# Dual_v12.net
KiCad netlist of a schematic drawn in EAGLE
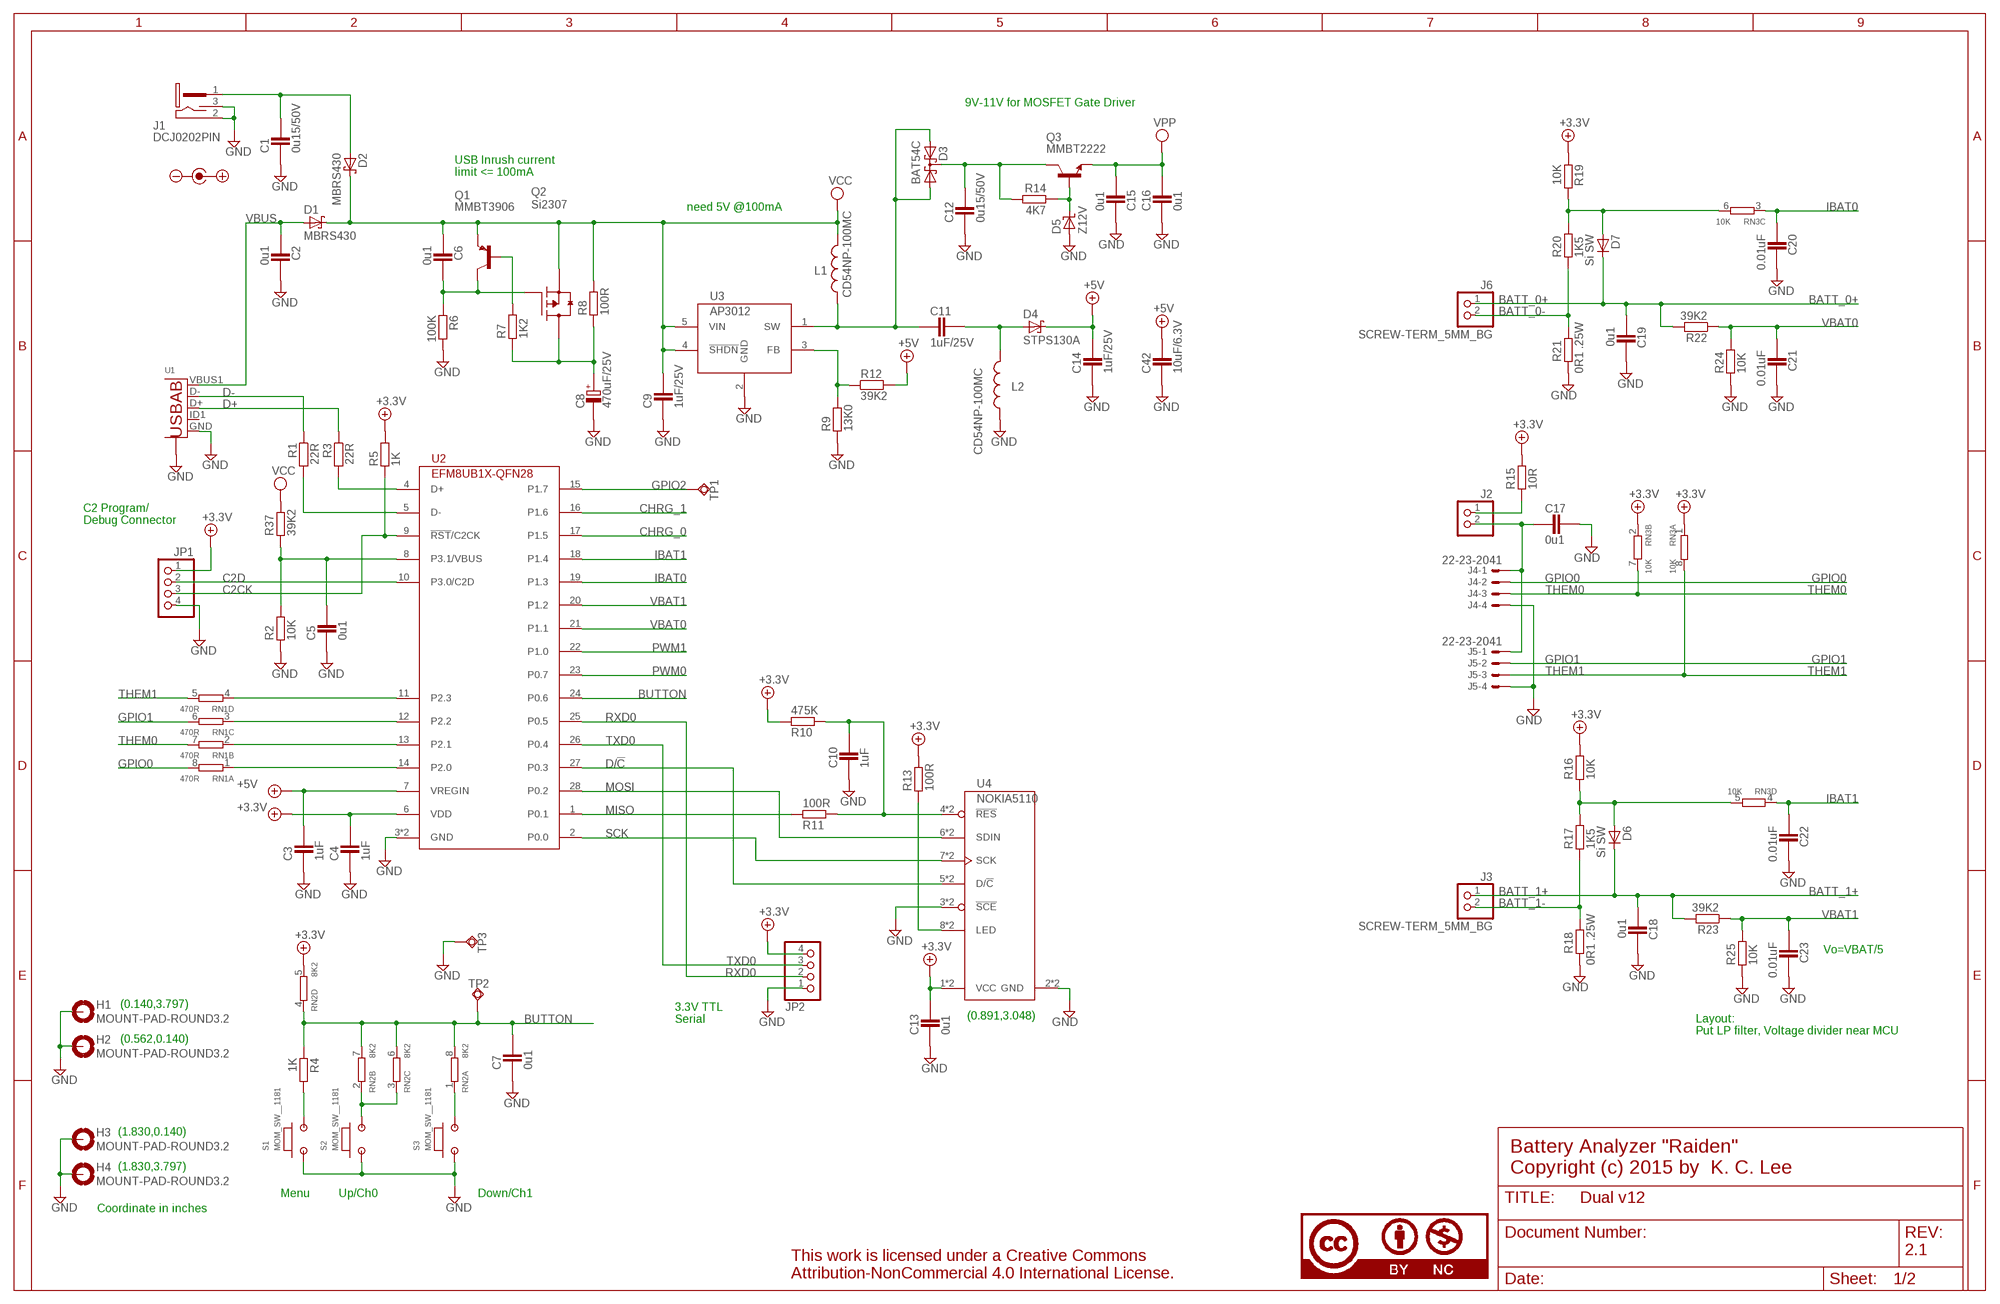
[diagram p0: schematic, sheet 1]
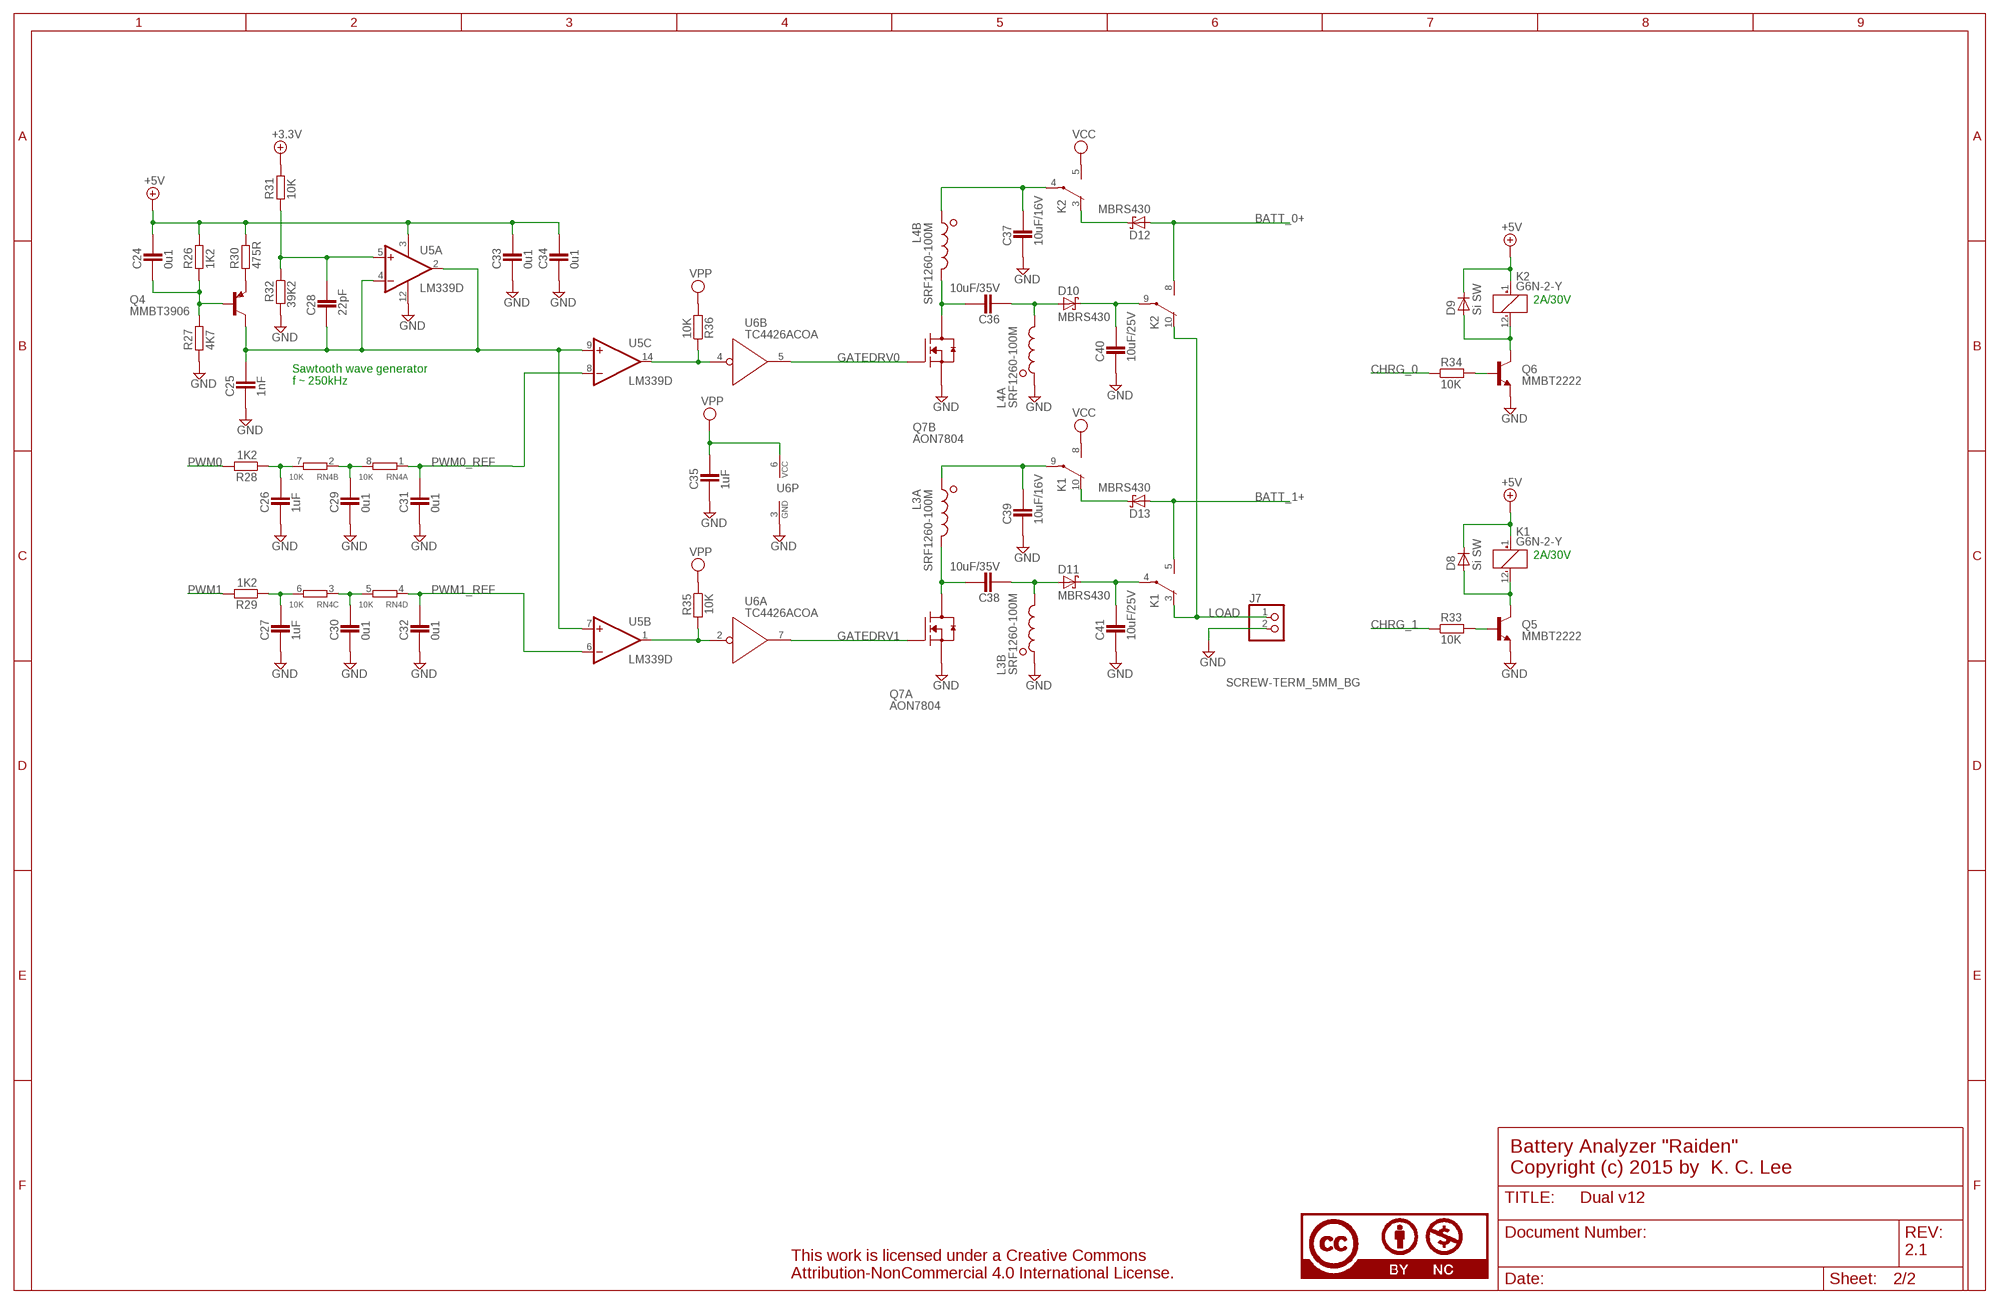
[diagram p1: schematic, sheet 2]

(export (version "E")
  (design (tool "Eeschema 10.0.6"))
  (components
    (comp (ref "C24")
      (value "0u1")
      (footprint "eagle-import:CAPC1608X92N")
      (fields (field (name "PARTNO") "STOCK: DK 490-1532-1-ND"))
      (libsource (lib "eagle-import") (part "CAPACITOR_0603"))
    )
    (comp (ref "C25")
      (value "1nF")
      (footprint "eagle-import:CAPC1608X92N")
      (fields (field (name "PARTNO") "DK: 311-1080-1-ND"))
      (libsource (lib "eagle-import") (part "CAPACITOR_0603"))
    )
    (comp (ref "C26")
      (value "1uF")
      (footprint "eagle-import:CAPC1608X92N")
      (fields (field (name "PARTNO") "STOCK: 1UF/10V 20% TDK"))
      (libsource (lib "eagle-import") (part "CAPACITOR_0603"))
    )
    (comp (ref "C27")
      (value "1uF")
      (footprint "eagle-import:CAPC1608X92N")
      (fields (field (name "PARTNO") "STOCK: 1UF/10V 20% TDK"))
      (libsource (lib "eagle-import") (part "CAPACITOR_0603"))
    )
    (comp (ref "C28")
      (value "22pF")
      (footprint "eagle-import:CAPC1608X92N")
      (fields (field (name "PARTNO") "STOCK: 22PF"))
      (libsource (lib "eagle-import") (part "CAPACITOR_0603"))
    )
    (comp (ref "C29")
      (value "0u1")
      (footprint "eagle-import:CAPC1005X60N")
      (fields (field (name "PARTNO") "STOCK: DK 587-1227-1-ND"))
      (libsource (lib "eagle-import") (part "CAPACITOR_0402"))
    )
    (comp (ref "C30")
      (value "0u1")
      (footprint "eagle-import:CAPC1005X60N")
      (fields (field (name "PARTNO") "STOCK: DK 587-1227-1-ND"))
      (libsource (lib "eagle-import") (part "CAPACITOR_0402"))
    )
    (comp (ref "C31")
      (value "0u1")
      (footprint "eagle-import:CAPC1005X60N")
      (fields (field (name "PARTNO") "STOCK: DK 587-1227-1-ND"))
      (libsource (lib "eagle-import") (part "CAPACITOR_0402"))
    )
    (comp (ref "C32")
      (value "0u1")
      (footprint "eagle-import:CAPC1005X60N")
      (fields (field (name "PARTNO") "STOCK: DK 587-1227-1-ND"))
      (libsource (lib "eagle-import") (part "CAPACITOR_0402"))
    )
    (comp (ref "C33")
      (value "0u1")
      (footprint "eagle-import:CAPC1608X92N")
      (fields (field (name "PARTNO") "STOCK: DK 490-1532-1-ND"))
      (libsource (lib "eagle-import") (part "CAPACITOR_0603"))
    )
    (comp (ref "C34")
      (value "0u1")
      (footprint "eagle-import:CAPC1608X92N")
      (fields (field (name "PARTNO") "STOCK: DK 490-1532-1-ND"))
      (libsource (lib "eagle-import") (part "CAPACITOR_0603"))
    )
    (comp (ref "C35")
      (value "1uF")
      (footprint "eagle-import:CAPC1608X92N")
      (fields (field (name "PARTNO") "STOCK: 1UF/10V 20% TDK"))
      (libsource (lib "eagle-import") (part "CAPACITOR_0603"))
    )
    (comp (ref "C36")
      (value "10uF/35V")
      (footprint "eagle-import:CAPC3215X168N")
      (fields (field (name "PARTNO") "DK: 490-9964-1-ND"))
      (libsource (lib "eagle-import") (part "CAPACITOR_1206"))
    )
    (comp (ref "C37")
      (value "10uF/16V")
      (footprint "eagle-import:CAPC3215X168N")
      (fields (field (name "PARTNO") "DK: 490-5525-1-ND"))
      (libsource (lib "eagle-import") (part "CAPACITOR_1206"))
    )
    (comp (ref "C38")
      (value "10uF/35V")
      (footprint "eagle-import:CAPC3215X168N")
      (fields (field (name "PARTNO") "DK: 490-9964-1-ND"))
      (libsource (lib "eagle-import") (part "CAPACITOR_1206"))
    )
    (comp (ref "C39")
      (value "10uF/16V")
      (footprint "eagle-import:CAPC3215X168N")
      (fields (field (name "PARTNO") "DK: 490-5525-1-ND"))
      (libsource (lib "eagle-import") (part "CAPACITOR_1206"))
    )
    (comp (ref "C40")
      (value "10uF/25V")
      (footprint "eagle-import:CAPC3215X168N")
      (fields (field (name "PARTNO") "DK: 490-5525-1-ND"))
      (libsource (lib "eagle-import") (part "CAPACITOR_1206"))
    )
    (comp (ref "C41")
      (value "10uF/25V")
      (footprint "eagle-import:CAPC3215X168N")
      (fields (field (name "PARTNO") "DK: 490-5525-1-ND"))
      (libsource (lib "eagle-import") (part "CAPACITOR_1206"))
    )
    (comp (ref "D8")
      (value "Si SW")
      (footprint "eagle-import:SOT95P280X135-3N")
      (fields (field (name "PARTNO") "STOCK: BAV99"))
      (libsource (lib "eagle-import") (part "DIODE_SOT-23"))
    )
    (comp (ref "D9")
      (value "Si SW")
      (footprint "eagle-import:SOT95P280X135-3N")
      (fields (field (name "PARTNO") "STOCK: BAV99"))
      (libsource (lib "eagle-import") (part "DIODE_SOT-23"))
    )
    (comp (ref "D10")
      (value "MBRS430")
      (footprint "eagle-import:DIOM7959X265N")
      (fields (field (name "PARTNO") "STOCK"))
      (libsource (lib "eagle-import") (part "SCHOTTKY_SMC"))
    )
    (comp (ref "D11")
      (value "MBRS430")
      (footprint "eagle-import:DIOM7959X265N")
      (fields (field (name "PARTNO") "STOCK"))
      (libsource (lib "eagle-import") (part "SCHOTTKY_SMC"))
    )
    (comp (ref "D12")
      (value "MBRS430")
      (footprint "eagle-import:DIOM7959X265N")
      (fields (field (name "PARTNO") "STOCK"))
      (libsource (lib "eagle-import") (part "SCHOTTKY_SMC"))
    )
    (comp (ref "D13")
      (value "MBRS430")
      (footprint "eagle-import:DIOM7959X265N")
      (fields (field (name "PARTNO") "STOCK"))
      (libsource (lib "eagle-import") (part "SCHOTTKY_SMC"))
    )
    (comp (ref "J7")
      (value "SCREW-TERM_5MM_BG")
      (footprint "eagle-import:1X02-5MM-BG")
      (fields (field (name "PARTNO") "BG: SKU170379"))
      (libsource (lib "eagle-import") (part "SCREW-TERM_5MM_BG"))
    )
    (comp (ref "K1")
      (value "G6N-2-Y")
      (footprint "eagle-import:NA")
      (fields (field (name "PARTNO") "STOCK"))
      (libsource (lib "eagle-import") (part "NA"))
    )
    (comp (ref "K2")
      (value "G6N-2-Y")
      (footprint "eagle-import:NA")
      (fields (field (name "PARTNO") "STOCK"))
      (libsource (lib "eagle-import") (part "NA"))
    )
    (comp (ref "L3")
      (value "SRF1260-100M")
      (footprint "eagle-import:SRF1260")
      (fields (field (name "PARTNO") "DK: SRF1260-100MCT-ND"))
      (libsource (lib "eagle-import") (part "SRF1260"))
    )
    (comp (ref "L4")
      (value "SRF1260-100M")
      (footprint "eagle-import:SRF1260")
      (fields (field (name "PARTNO") "DK: SRF1260-100MCT-ND"))
      (libsource (lib "eagle-import") (part "SRF1260"))
    )
    (comp (ref "Q4")
      (value "MMBT3906")
      (footprint "eagle-import:SOT95P280X135-3N")
      (fields (field (name "PARTNO") "STOCK:MMBT3906"))
      (libsource (lib "eagle-import") (part "PNP_SOT-23"))
    )
    (comp (ref "Q5")
      (value "MMBT2222")
      (footprint "eagle-import:SOT95P280X135-3N")
      (fields (field (name "PARTNO") "STOCK: MMBT2222"))
      (libsource (lib "eagle-import") (part "NPN_SOT-23"))
    )
    (comp (ref "Q6")
      (value "MMBT2222")
      (footprint "eagle-import:SOT95P280X135-3N")
      (fields (field (name "PARTNO") "STOCK: MMBT2222"))
      (libsource (lib "eagle-import") (part "NPN_SOT-23"))
    )
    (comp (ref "Q7")
      (value "AON7804")
      (footprint "eagle-import:DFN3X3")
      (fields (field (name "PARTNO") "DK: 785-1586-1-ND"))
      (libsource (lib "eagle-import") (part "AON7804"))
    )
    (comp (ref "R26")
      (value "1K2")
      (footprint "eagle-import:RESC1608X55N")
      (fields (field (name "PARTNO") "STOCK: 1K21 1%"))
      (libsource (lib "eagle-import") (part "RESISTOR_0603"))
    )
    (comp (ref "R27")
      (value "4K7")
      (footprint "eagle-import:RESC1608X55N")
      (fields (field (name "PARTNO") "STOCK:4K75 1%"))
      (libsource (lib "eagle-import") (part "RESISTOR_0603"))
    )
    (comp (ref "R28")
      (value "1K2")
      (footprint "eagle-import:RESC1608X55N")
      (fields (field (name "PARTNO") "STOCK: 1K21 1%"))
      (libsource (lib "eagle-import") (part "RESISTOR_0603"))
    )
    (comp (ref "R29")
      (value "1K2")
      (footprint "eagle-import:RESC1608X55N")
      (fields (field (name "PARTNO") "STOCK: 1K21 1%"))
      (libsource (lib "eagle-import") (part "RESISTOR_0603"))
    )
    (comp (ref "R30")
      (value "475R")
      (footprint "eagle-import:RESC1608X55N")
      (fields (field (name "PARTNO") "STOCK: DK 1276-4620-1-ND"))
      (libsource (lib "eagle-import") (part "RESISTOR_0603"))
    )
    (comp (ref "R31")
      (value "10K")
      (footprint "eagle-import:RESC1608X55N")
      (fields (field (name "PARTNO") "STOCK: 10K 1%"))
      (libsource (lib "eagle-import") (part "RESISTOR_0603"))
    )
    (comp (ref "R32")
      (value "39K2")
      (footprint "eagle-import:RESC1608X55N")
      (fields (field (name "PARTNO") "DK: 311-39.2KHRCT-ND"))
      (libsource (lib "eagle-import") (part "RESISTOR_0603"))
    )
    (comp (ref "R33")
      (value "10K")
      (footprint "eagle-import:RESC1608X55N")
      (fields (field (name "PARTNO") "STOCK: 10K 1%"))
      (libsource (lib "eagle-import") (part "RESISTOR_0603"))
    )
    (comp (ref "R34")
      (value "10K")
      (footprint "eagle-import:RESC1608X55N")
      (fields (field (name "PARTNO") "STOCK: 10K 1%"))
      (libsource (lib "eagle-import") (part "RESISTOR_0603"))
    )
    (comp (ref "R35")
      (value "10K")
      (footprint "eagle-import:RESC1608X55N")
      (fields (field (name "PARTNO") "STOCK: 10K 1%"))
      (libsource (lib "eagle-import") (part "RESISTOR_0603"))
    )
    (comp (ref "R36")
      (value "10K")
      (footprint "eagle-import:RESC1608X55N")
      (fields (field (name "PARTNO") "STOCK: 10K 1%"))
      (libsource (lib "eagle-import") (part "RESISTOR_0603"))
    )
    (comp (ref "RN4")
      (value "10K")
      (footprint "eagle-import:CAT16")
      (fields (field (name "PARTNO") "STOCK: DK CAY16-103J4GLFCT-ND"))
      (libsource (lib "eagle-import") (part "4R-NCAT16"))
    )
    (comp (ref "U$2")
      (value "CCNONE")
      (footprint "eagle-import:CC-NONE")
      (libsource (lib "eagle-import") (part "CCNONE"))
    )
    (comp (ref "U5")
      (value "LM339D")
      (footprint "eagle-import:SO14")
      (fields (field (name "PARTNO") "STOCK"))
      (libsource (lib "eagle-import") (part "LM339D"))
    )
    (comp (ref "U6")
      (value "TC4426ACOA")
      (footprint "eagle-import:SOIC8")
      (fields (field (name "PARTNO") "DK: TC4426ACOA-ND"))
      (libsource (lib "eagle-import") (part "TC4426AMF"))
    )
    (comp (ref "C1")
      (value "0u15/50V")
      (footprint "eagle-import:CAP2012X70N")
      (fields (field (name "PARTNO") "STOCK: 0.15UF/50V10%"))
      (libsource (lib "eagle-import") (part "CAPACITOR_0805N"))
    )
    (comp (ref "C2")
      (value "0u1")
      (footprint "eagle-import:CAPC1608X92N")
      (fields (field (name "PARTNO") "STOCK: DK 490-1532-1-ND"))
      (libsource (lib "eagle-import") (part "CAPACITOR_0603"))
    )
    (comp (ref "C3")
      (value "1uF")
      (footprint "eagle-import:CAPC1005X60N")
      (fields (field (name "PARTNO") "DK: 490-10435-1-ND"))
      (libsource (lib "eagle-import") (part "CAPACITOR_0402"))
    )
    (comp (ref "C4")
      (value "1uF")
      (footprint "eagle-import:CAPC1005X60N")
      (fields (field (name "PARTNO") "DK: 490-10435-1-ND"))
      (libsource (lib "eagle-import") (part "CAPACITOR_0402"))
    )
    (comp (ref "C5")
      (value "0u1")
      (footprint "eagle-import:CAPC1005X60N")
      (fields (field (name "PARTNO") "STOCK: DK 587-1227-1-ND"))
      (libsource (lib "eagle-import") (part "CAPACITOR_0402"))
    )
    (comp (ref "C6")
      (value "0u1")
      (footprint "eagle-import:CAPC1608X92N")
      (fields (field (name "PARTNO") "STOCK: DK 490-1532-1-ND"))
      (libsource (lib "eagle-import") (part "CAPACITOR_0603"))
    )
    (comp (ref "C7")
      (value "0u1")
      (footprint "eagle-import:CAPC1608X92N")
      (fields (field (name "PARTNO") "STOCK: DK 490-1532-1-ND"))
      (libsource (lib "eagle-import") (part "CAPACITOR_0603"))
    )
    (comp (ref "C8")
      (value "470uF/25V")
      (footprint "eagle-import:CAPAE1030X1020N")
      (fields (field (name "PARTNO") "STOCK"))
      (libsource (lib "eagle-import") (part "POLARISED_CASE_G"))
    )
    (comp (ref "C9")
      (value "1uF/25V")
      (footprint "eagle-import:CAP2012X70N")
      (fields (field (name "PARTNO") "DK: 311-1456-1-ND"))
      (libsource (lib "eagle-import") (part "CAPACITOR_0805N"))
    )
    (comp (ref "C10")
      (value "1uF")
      (footprint "eagle-import:CAPC1608X92N")
      (fields (field (name "PARTNO") "STOCK: 1UF/10V 20% TDK"))
      (libsource (lib "eagle-import") (part "CAPACITOR_0603"))
    )
    (comp (ref "C11")
      (value "1uF/25V")
      (footprint "eagle-import:CAP2012X70N")
      (fields (field (name "PARTNO") "DK: 311-1456-1-ND"))
      (libsource (lib "eagle-import") (part "CAPACITOR_0805N"))
    )
    (comp (ref "C12")
      (value "0u15/50V")
      (footprint "eagle-import:CAP2012X70N")
      (fields (field (name "PARTNO") "STOCK: 0.15UF/50V10%"))
      (libsource (lib "eagle-import") (part "CAPACITOR_0805N"))
    )
    (comp (ref "C13")
      (value "0u1")
      (footprint "eagle-import:CAPC1608X92N")
      (fields (field (name "PARTNO") "STOCK: DK 490-1532-1-ND"))
      (libsource (lib "eagle-import") (part "CAPACITOR_0603"))
    )
    (comp (ref "C14")
      (value "1uF/25V")
      (footprint "eagle-import:CAP2012X70N")
      (fields (field (name "PARTNO") "DK: 311-1456-1-ND"))
      (libsource (lib "eagle-import") (part "CAPACITOR_0805N"))
    )
    (comp (ref "C15")
      (value "0u1")
      (footprint "eagle-import:CAPC1608X92N")
      (fields (field (name "PARTNO") "STOCK: DK 490-1532-1-ND"))
      (libsource (lib "eagle-import") (part "CAPACITOR_0603"))
    )
    (comp (ref "C16")
      (value "0u1")
      (footprint "eagle-import:CAPC1608X92N")
      (fields (field (name "PARTNO") "STOCK: DK 490-1532-1-ND"))
      (libsource (lib "eagle-import") (part "CAPACITOR_0603"))
    )
    (comp (ref "C17")
      (value "0u1")
      (footprint "eagle-import:CAPC1608X92N")
      (fields (field (name "PARTNO") "STOCK: DK 490-1532-1-ND"))
      (libsource (lib "eagle-import") (part "CAPACITOR_0603"))
    )
    (comp (ref "C18")
      (value "0u1")
      (footprint "eagle-import:CAPC1608X92N")
      (fields (field (name "PARTNO") "STOCK: DK 490-1532-1-ND"))
      (libsource (lib "eagle-import") (part "CAPACITOR_0603"))
    )
    (comp (ref "C19")
      (value "0u1")
      (footprint "eagle-import:CAPC1608X92N")
      (fields (field (name "PARTNO") "STOCK: DK 490-1532-1-ND"))
      (libsource (lib "eagle-import") (part "CAPACITOR_0603"))
    )
    (comp (ref "C20")
      (value "0.01uF")
      (footprint "eagle-import:CAPC1608X92N")
      (fields (field (name "PARTNO") "DK: 311-1085-1-ND"))
      (libsource (lib "eagle-import") (part "CAPACITOR_0603"))
    )
    (comp (ref "C21")
      (value "0.01uF")
      (footprint "eagle-import:CAPC1608X92N")
      (fields (field (name "PARTNO") "DK: 311-1085-1-ND"))
      (libsource (lib "eagle-import") (part "CAPACITOR_0603"))
    )
    (comp (ref "C22")
      (value "0.01uF")
      (footprint "eagle-import:CAPC1608X92N")
      (fields (field (name "PARTNO") "DK: 311-1085-1-ND"))
      (libsource (lib "eagle-import") (part "CAPACITOR_0603"))
    )
    (comp (ref "C23")
      (value "0.01uF")
      (footprint "eagle-import:CAPC1608X92N")
      (fields (field (name "PARTNO") "DK: 311-1085-1-ND"))
      (libsource (lib "eagle-import") (part "CAPACITOR_0603"))
    )
    (comp (ref "C42")
      (value "10uF/6.3V")
      (footprint "eagle-import:CAP2012X70N")
      (fields (field (name "PARTNO") "DK: 490-5525-1-ND"))
      (libsource (lib "eagle-import") (part "CAPACITOR_0805N"))
    )
    (comp (ref "D1")
      (value "MBRS430")
      (footprint "eagle-import:DIOM7959X265N")
      (fields (field (name "PARTNO") "STOCK"))
      (libsource (lib "eagle-import") (part "SCHOTTKY_SMC"))
    )
    (comp (ref "D2")
      (value "MBRS430")
      (footprint "eagle-import:DIOM7959X265N")
      (fields (field (name "PARTNO") "STOCK"))
      (libsource (lib "eagle-import") (part "SCHOTTKY_SMC"))
    )
    (comp (ref "D3")
      (value "BAT54C")
      (footprint "eagle-import:SOT95P280X135-3N")
      (fields (field (name "PARTNO") "STOCK"))
      (libsource (lib "eagle-import") (part "BAT54C"))
    )
    (comp (ref "D4")
      (value "STPS130A")
      (footprint "eagle-import:DIOM5326X292N")
      (fields (field (name "PARTNO") "DK: 497-3755-1-ND"))
      (libsource (lib "eagle-import") (part "SCHOTTKY_SMA"))
    )
    (comp (ref "D5")
      (value "Z12V")
      (footprint "eagle-import:SOT95P280X135-3N")
      (fields (field (name "PARTNO") "STOCK"))
      (libsource (lib "eagle-import") (part "ZENER_SOT-23"))
    )
    (comp (ref "D6")
      (value "Si SW")
      (footprint "eagle-import:SOT95P280X135-3N")
      (fields (field (name "PARTNO") "STOCK: BAV99"))
      (libsource (lib "eagle-import") (part "DIODE_SOT-23"))
    )
    (comp (ref "D7")
      (value "Si SW")
      (footprint "eagle-import:SOT95P280X135-3N")
      (fields (field (name "PARTNO") "STOCK: BAV99"))
      (libsource (lib "eagle-import") (part "DIODE_SOT-23"))
    )
    (comp (ref "H1")
      (value "MOUNT-PAD-ROUND3.2")
      (footprint "eagle-import:3,2-PAD")
      (libsource (lib "eagle-import") (part "MOUNT-PAD-ROUND3.2"))
    )
    (comp (ref "H2")
      (value "MOUNT-PAD-ROUND3.2")
      (footprint "eagle-import:3,2-PAD")
      (libsource (lib "eagle-import") (part "MOUNT-PAD-ROUND3.2"))
    )
    (comp (ref "H3")
      (value "MOUNT-PAD-ROUND3.2")
      (footprint "eagle-import:3,2-PAD")
      (libsource (lib "eagle-import") (part "MOUNT-PAD-ROUND3.2"))
    )
    (comp (ref "H4")
      (value "MOUNT-PAD-ROUND3.2")
      (footprint "eagle-import:3,2-PAD")
      (libsource (lib "eagle-import") (part "MOUNT-PAD-ROUND3.2"))
    )
    (comp (ref "J1")
      (value "DCJ0202PIN")
      (footprint "eagle-import:PJ-102A")
      (fields (field (name "PARTNO") "STOCK: DK CP-102A-ND"))
      (libsource (lib "eagle-import") (part "DCJ0202PIN"))
    )
    (comp (ref "J2")
      (value "PINHD-1X2_2.54")
      (footprint "eagle-import:1X02")
      (fields (field (name "PARTNO") "BG: SKU038984"))
      (libsource (lib "eagle-import") (part "PINHD-1X2_2.54"))
    )
    (comp (ref "J3")
      (value "SCREW-TERM_5MM_BG")
      (footprint "eagle-import:1X02-5MM-BG")
      (fields (field (name "PARTNO") "BG: SKU170379"))
      (libsource (lib "eagle-import") (part "SCREW-TERM_5MM_BG"))
    )
    (comp (ref "J4")
      (value "22-23-2041")
      (footprint "eagle-import:22-23-2041")
      (fields (field (name "MF") "MOLEX") (field (name "PARTNO") "DK: A19431-ND"))
      (libsource (lib "eagle-import") (part "22-23-2041"))
    )
    (comp (ref "J5")
      (value "22-23-2041")
      (footprint "eagle-import:22-23-2041")
      (fields (field (name "MF") "MOLEX") (field (name "PARTNO") "DK: A19431-ND"))
      (libsource (lib "eagle-import") (part "22-23-2041"))
    )
    (comp (ref "J6")
      (value "SCREW-TERM_5MM_BG")
      (footprint "eagle-import:1X02-5MM-BG")
      (fields (field (name "PARTNO") "BG: SKU170379"))
      (libsource (lib "eagle-import") (part "SCREW-TERM_5MM_BG"))
    )
    (comp (ref "JP1")
      (value "PINHD-1X4_2.54")
      (footprint "eagle-import:1X04")
      (fields (field (name "PARTNO") "BG: SKU038984"))
      (libsource (lib "eagle-import") (part "PINHD-1X4_2.54"))
    )
    (comp (ref "JP2")
      (value "PINHD-1X4_2.54-90°")
      (footprint "eagle-import:1X04-RA")
      (fields (field (name "PARTNO") "STOCK"))
      (libsource (lib "eagle-import") (part "PINHD-1X4_2.54-90°"))
    )
    (comp (ref "L1")
      (value "CD54NP-100MC")
      (footprint "eagle-import:CD54")
      (fields (field (name "PARTNO") "DK: 587-1626-1-ND"))
      (libsource (lib "eagle-import") (part "CD54"))
    )
    (comp (ref "L2")
      (value "CD54NP-100MC")
      (footprint "eagle-import:CD54")
      (fields (field (name "PARTNO") "DK: 587-1626-1-ND"))
      (libsource (lib "eagle-import") (part "CD54"))
    )
    (comp (ref "Q1")
      (value "MMBT3906")
      (footprint "eagle-import:SOT95P280X135-3N")
      (fields (field (name "PARTNO") "STOCK:MMBT3906"))
      (libsource (lib "eagle-import") (part "PNP_SOT-23"))
    )
    (comp (ref "Q2")
      (value "Si2307")
      (footprint "eagle-import:SOT95P280X135-3N")
      (fields (field (name "PARTNO") "STOCK: SI2307DS"))
      (libsource (lib "eagle-import") (part "MOSFET-PCH_SOT-23"))
    )
    (comp (ref "Q3")
      (value "MMBT2222")
      (footprint "eagle-import:SOT95P280X135-3N")
      (fields (field (name "PARTNO") "STOCK: MMBT2222"))
      (libsource (lib "eagle-import") (part "NPN_SOT-23"))
    )
    (comp (ref "R1")
      (value "22R")
      (footprint "eagle-import:RESC1608X55N")
      (fields (field (name "PARTNO") "STOCK: DK 1276-3497-1-ND"))
      (libsource (lib "eagle-import") (part "RESISTOR_0603"))
    )
    (comp (ref "R2")
      (value "10K")
      (footprint "eagle-import:RESC1608X55N")
      (fields (field (name "PARTNO") "STOCK: 10K 1%"))
      (libsource (lib "eagle-import") (part "RESISTOR_0603"))
    )
    (comp (ref "R3")
      (value "22R")
      (footprint "eagle-import:RESC1608X55N")
      (fields (field (name "PARTNO") "STOCK: DK 1276-3497-1-ND"))
      (libsource (lib "eagle-import") (part "RESISTOR_0603"))
    )
    (comp (ref "R4")
      (value "1K")
      (footprint "eagle-import:RESC1608X55N")
      (fields (field (name "PARTNO") "STOCK: DK 1276-3484-1-ND"))
      (libsource (lib "eagle-import") (part "RESISTOR_0603"))
    )
    (comp (ref "R5")
      (value "1K")
      (footprint "eagle-import:RESC1005X40AN")
      (fields (field (name "PARTNO") "DK: 311-1.00KLRCT-ND"))
      (libsource (lib "eagle-import") (part "RESISTOR_0402"))
    )
    (comp (ref "R6")
      (value "100K")
      (footprint "eagle-import:RESC1608X55N")
      (fields (field (name "PARTNO") "STOCK: DK311-100KHRCT-ND"))
      (libsource (lib "eagle-import") (part "RESISTOR_0603"))
    )
    (comp (ref "R7")
      (value "1K2")
      (footprint "eagle-import:RESC1608X55N")
      (fields (field (name "PARTNO") "STOCK: 1K21 1%"))
      (libsource (lib "eagle-import") (part "RESISTOR_0603"))
    )
    (comp (ref "R8")
      (value "100R")
      (footprint "eagle-import:RESC2012X70N")
      (fields (field (name "PARTNO") "STOCK"))
      (libsource (lib "eagle-import") (part "RESISTOR_0805"))
    )
    (comp (ref "R9")
      (value "13K0")
      (footprint "eagle-import:RESC1608X55N")
      (fields (field (name "PARTNO") "DK: 311-13.0KHRCT-ND"))
      (libsource (lib "eagle-import") (part "RESISTOR_0603"))
    )
    (comp (ref "R10")
      (value "475K")
      (footprint "eagle-import:RESC1608X55N")
      (fields (field (name "PARTNO") "STOCK: P475KHCT-ND"))
      (libsource (lib "eagle-import") (part "RESISTOR_0603"))
    )
    (comp (ref "R11")
      (value "100R")
      (footprint "eagle-import:RESC1608X55N")
      (fields (field (name "PARTNO") "STOCK"))
      (libsource (lib "eagle-import") (part "RESISTOR_0603"))
    )
    (comp (ref "R12")
      (value "39K2")
      (footprint "eagle-import:RESC1608X55N")
      (fields (field (name "PARTNO") "DK: 311-39.2KHRCT-ND"))
      (libsource (lib "eagle-import") (part "RESISTOR_0603"))
    )
    (comp (ref "R13")
      (value "100R")
      (footprint "eagle-import:RESC1608X55N")
      (fields (field (name "PARTNO") "STOCK"))
      (libsource (lib "eagle-import") (part "RESISTOR_0603"))
    )
    (comp (ref "R14")
      (value "4K7")
      (footprint "eagle-import:RESC1608X55N")
      (fields (field (name "PARTNO") "STOCK:4K75 1%"))
      (libsource (lib "eagle-import") (part "RESISTOR_0603"))
    )
    (comp (ref "R15")
      (value "10R")
      (footprint "eagle-import:RESC1608X55N")
      (fields (field (name "PARTNO") "STOCK: 10R 1%"))
      (libsource (lib "eagle-import") (part "RESISTOR_0603"))
    )
    (comp (ref "R16")
      (value "10K")
      (footprint "eagle-import:RESC1608X55N")
      (fields (field (name "PARTNO") "STOCK: 10K 1%"))
      (libsource (lib "eagle-import") (part "RESISTOR_0603"))
    )
    (comp (ref "R17")
      (value "1K5")
      (footprint "eagle-import:RESC1608X55N")
      (fields (field (name "PARTNO") "STOCK: DKRHM1.50KCFCT-ND"))
      (libsource (lib "eagle-import") (part "RESISTOR_0603"))
    )
    (comp (ref "R18")
      (value "0R1 .25W")
      (footprint "eagle-import:RESC3115X70N")
      (fields (field (name "PARTNO") "STOCK: DK73L4R10JCT-ND"))
      (libsource (lib "eagle-import") (part "RESISTOR_1206"))
    )
    (comp (ref "R19")
      (value "10K")
      (footprint "eagle-import:RESC1608X55N")
      (fields (field (name "PARTNO") "STOCK: 10K 1%"))
      (libsource (lib "eagle-import") (part "RESISTOR_0603"))
    )
    (comp (ref "R20")
      (value "1K5")
      (footprint "eagle-import:RESC1608X55N")
      (fields (field (name "PARTNO") "STOCK: DKRHM1.50KCFCT-ND"))
      (libsource (lib "eagle-import") (part "RESISTOR_0603"))
    )
    (comp (ref "R21")
      (value "0R1 .25W")
      (footprint "eagle-import:RESC3115X70N")
      (fields (field (name "PARTNO") "STOCK: DK73L4R10JCT-ND"))
      (libsource (lib "eagle-import") (part "RESISTOR_1206"))
    )
    (comp (ref "R22")
      (value "39K2")
      (footprint "eagle-import:RESC1608X55N")
      (fields (field (name "PARTNO") "DK: 311-39.2KHRCT-ND"))
      (libsource (lib "eagle-import") (part "RESISTOR_0603"))
    )
    (comp (ref "R23")
      (value "39K2")
      (footprint "eagle-import:RESC1608X55N")
      (fields (field (name "PARTNO") "DK: 311-39.2KHRCT-ND"))
      (libsource (lib "eagle-import") (part "RESISTOR_0603"))
    )
    (comp (ref "R24")
      (value "10K")
      (footprint "eagle-import:RESC1608X55N")
      (fields (field (name "PARTNO") "STOCK: 10K 1%"))
      (libsource (lib "eagle-import") (part "RESISTOR_0603"))
    )
    (comp (ref "R25")
      (value "10K")
      (footprint "eagle-import:RESC1608X55N")
      (fields (field (name "PARTNO") "STOCK: 10K 1%"))
      (libsource (lib "eagle-import") (part "RESISTOR_0603"))
    )
    (comp (ref "R37")
      (value "39K2")
      (footprint "eagle-import:RESC1608X55N")
      (fields (field (name "PARTNO") "DK: 311-39.2KHRCT-ND"))
      (libsource (lib "eagle-import") (part "RESISTOR_0603"))
    )
    (comp (ref "RN1")
      (value "470R")
      (footprint "eagle-import:CAT16")
      (fields (field (name "PARTNO") "DK: YC164J-470CT-ND"))
      (libsource (lib "eagle-import") (part "4R-NCAT16"))
    )
    (comp (ref "RN2")
      (value "8K2")
      (footprint "eagle-import:CAT16")
      (fields
        (field (name "OC_FARNELL") "unknown")
        (field (name "OC_NEWARK") "unknown")
        (field (name "PARTNO") "STOCK")
      )
      (libsource (lib "eagle-import") (part "4R-NCAT16"))
    )
    (comp (ref "RN3")
      (value "10K")
      (footprint "eagle-import:CAT16")
      (fields (field (name "PARTNO") "STOCK: DK CAY16-103J4GLFCT-ND"))
      (libsource (lib "eagle-import") (part "4R-NCAT16"))
    )
    (comp (ref "S1")
      (value "MOM_SW__1181")
      (footprint "eagle-import:MOM-1181")
      (fields (field (name "PARTNO") "BG: SKU156899"))
      (libsource (lib "eagle-import") (part "MOM_SW__1181"))
    )
    (comp (ref "S2")
      (value "MOM_SW__1181")
      (footprint "eagle-import:MOM-1181")
      (fields (field (name "PARTNO") "BG: SKU156899"))
      (libsource (lib "eagle-import") (part "MOM_SW__1181"))
    )
    (comp (ref "S3")
      (value "MOM_SW__1181")
      (footprint "eagle-import:MOM-1181")
      (fields (field (name "PARTNO") "BG: SKU156899"))
      (libsource (lib "eagle-import") (part "MOM_SW__1181"))
    )
    (comp (ref "TP1")
      (value "TPSQTP08R")
      (footprint "eagle-import:TP08R")
      (libsource (lib "eagle-import") (part "TPSQTP08R"))
    )
    (comp (ref "TP2")
      (value "TPSQTP14SQ")
      (footprint "eagle-import:TP14SQ")
      (libsource (lib "eagle-import") (part "TPSQTP14SQ"))
    )
    (comp (ref "TP3")
      (value "TPSQTP14SQ")
      (footprint "eagle-import:TP14SQ")
      (libsource (lib "eagle-import") (part "TPSQTP14SQ"))
    )
    (comp (ref "U$1")
      (value "CC100%")
      (footprint "eagle-import:CC-100")
      (libsource (lib "eagle-import") (part "CC100%"))
    )
    (comp (ref "U$3")
      (value "POLARITY")
      (footprint "eagle-import:POLARITY")
      (libsource (lib "eagle-import") (part "POLARITY"))
    )
    (comp (ref "U1")
      (value "USB-ABBG")
      (footprint "eagle-import:USB-AB-MICRO-SMD_V03_SF")
      (fields (field (name "PARTNO") "DX: SKU134132"))
      (libsource (lib "eagle-import") (part "USB-ABBG"))
    )
    (comp (ref "U2")
      (value "EFM8UB1X-QFN28")
      (footprint "eagle-import:QFN-28")
      (fields (field (name "PARTNO") "DK: 336-3183-5-ND"))
      (libsource (lib "eagle-import") (part "EFM8UB1X-QFN28"))
    )
    (comp (ref "U3")
      (value "AP3012")
      (footprint "eagle-import:SOT23-5")
      (fields (field (name "PARTNO") "DK: AP3012KTR-G1DICT-ND"))
      (libsource (lib "eagle-import") (part "AP3012"))
    )
    (comp (ref "U4")
      (value "NOKIA5110")
      (footprint "eagle-import:NOKIA5110-BOTH")
      (fields (field (name "PARTNO") "BG: SKU091069"))
      (libsource (lib "eagle-import") (part "NOKIA5110"))
    )
  )
  (nets
    (net (code "1") (name "+3.3V") (class "Default")
      (node (ref "C13") (pin "2") (pinfunction "2_2") (pintype "passive"))
      (node (ref "C4") (pin "2") (pinfunction "2_2") (pintype "passive"))
      (node (ref "JP1") (pin "1") (pinfunction "1_1") (pintype "passive"))
      (node (ref "JP2") (pin "4") (pinfunction "4_4") (pintype "passive"))
      (node (ref "R10") (pin "1") (pinfunction "1_1") (pintype "passive"))
      (node (ref "R13") (pin "2") (pinfunction "2_2") (pintype "passive"))
      (node (ref "R15") (pin "2") (pinfunction "2_2") (pintype "passive"))
      (node (ref "R16") (pin "2") (pinfunction "2_2") (pintype "passive"))
      (node (ref "R19") (pin "1") (pinfunction "1_1") (pintype "passive"))
      (node (ref "R31") (pin "2") (pinfunction "2_2") (pintype "passive"))
      (node (ref "R5") (pin "2") (pinfunction "2_2") (pintype "passive"))
      (node (ref "RN2") (pin "5") (pinfunction "2_5") (pintype "passive"))
      (node (ref "RN3") (pin "1") (pinfunction "1_1") (pintype "passive"))
      (node (ref "RN3") (pin "2") (pinfunction "1_2") (pintype "passive"))
      (node (ref "U2") (pin "6") (pinfunction "VDD_6") (pintype "bidirectional"))
      (node (ref "U4") (pin "1") (pinfunction "VCC_1") (pintype "input"))
      (node (ref "U4") (pin "9") (pinfunction "VCC_9") (pintype "input"))
    )
    (net (code "2") (name "+5V") (class "Default")
      (node (ref "C14") (pin "2") (pinfunction "2_2") (pintype "passive"))
      (node (ref "C24") (pin "2") (pinfunction "2_2") (pintype "passive"))
      (node (ref "C3") (pin "2") (pinfunction "2_2") (pintype "passive"))
      (node (ref "C33") (pin "2") (pinfunction "2_2") (pintype "passive"))
      (node (ref "C34") (pin "2") (pinfunction "2_2") (pintype "passive"))
      (node (ref "C42") (pin "2") (pinfunction "2_2") (pintype "passive"))
      (node (ref "D4") (pin "K") (pinfunction "K_K") (pintype "passive"))
      (node (ref "D8") (pin "3") (pinfunction "K_3") (pintype "passive"))
      (node (ref "D9") (pin "3") (pinfunction "K_3") (pintype "passive"))
      (node (ref "K1") (pin "1") (pinfunction "+_1") (pintype "passive"))
      (node (ref "K2") (pin "1") (pinfunction "+_1") (pintype "passive"))
      (node (ref "R12") (pin "2") (pinfunction "2_2") (pintype "passive"))
      (node (ref "R26") (pin "2") (pinfunction "2_2") (pintype "passive"))
      (node (ref "R30") (pin "2") (pinfunction "2_2") (pintype "passive"))
      (node (ref "U2") (pin "7") (pinfunction "VREGIN_7") (pintype "bidirectional"))
      (node (ref "U5") (pin "3") (pinfunction "V+_3") (pintype "power_in"))
    )
    (net (code "3") (name "BATT_0+") (class "Default")
      (node (ref "C19") (pin "1") (pinfunction "1_1") (pintype "passive"))
      (node (ref "D12") (pin "A") (pinfunction "A_A") (pintype "passive"))
      (node (ref "D7") (pin "3") (pinfunction "K_3") (pintype "passive"))
      (node (ref "J6") (pin "1") (pinfunction "1_1") (pintype "passive"))
      (node (ref "K2") (pin "8") (pinfunction "S_8") (pintype "passive"))
      (node (ref "R22") (pin "2") (pinfunction "2_2") (pintype "passive"))
    )
    (net (code "4") (name "BATT_0-") (class "Default")
      (node (ref "J6") (pin "2") (pinfunction "2_2") (pintype "passive"))
      (node (ref "R20") (pin "1") (pinfunction "1_1") (pintype "passive"))
      (node (ref "R21") (pin "2") (pinfunction "2_2") (pintype "passive"))
    )
    (net (code "5") (name "BATT_1+") (class "Default")
      (node (ref "C18") (pin "1") (pinfunction "1_1") (pintype "passive"))
      (node (ref "D13") (pin "A") (pinfunction "A_A") (pintype "passive"))
      (node (ref "D6") (pin "3") (pinfunction "K_3") (pintype "passive"))
      (node (ref "J3") (pin "1") (pinfunction "1_1") (pintype "passive"))
      (node (ref "K1") (pin "5") (pinfunction "S_5") (pintype "passive"))
      (node (ref "R23") (pin "2") (pinfunction "2_2") (pintype "passive"))
    )
    (net (code "6") (name "BATT_1-") (class "Default")
      (node (ref "J3") (pin "2") (pinfunction "2_2") (pintype "passive"))
      (node (ref "R17") (pin "1") (pinfunction "1_1") (pintype "passive"))
      (node (ref "R18") (pin "2") (pinfunction "2_2") (pintype "passive"))
    )
    (net (code "7") (name "BUTTON") (class "Default")
      (node (ref "C7") (pin "2") (pinfunction "2_2") (pintype "passive"))
      (node (ref "R4") (pin "1") (pinfunction "1_1") (pintype "passive"))
      (node (ref "RN2") (pin "4") (pinfunction "1_4") (pintype "passive"))
      (node (ref "RN2") (pin "6") (pinfunction "2_6") (pintype "passive"))
      (node (ref "RN2") (pin "7") (pinfunction "2_7") (pintype "passive"))
      (node (ref "RN2") (pin "8") (pinfunction "2_8") (pintype "passive"))
      (node (ref "TP2") (pin "TP") (pinfunction "TP_TP") (pintype "input"))
      (node (ref "U2") (pin "24") (pinfunction "P0.6_24") (pintype "bidirectional"))
    )
    (net (code "8") (name "C2CK") (class "Default")
      (node (ref "JP1") (pin "3") (pinfunction "3_3") (pintype "passive"))
      (node (ref "R5") (pin "1") (pinfunction "1_1") (pintype "passive"))
      (node (ref "U2") (pin "9") (pinfunction "~{RST}/C2CK_9") (pintype "bidirectional"))
    )
    (net (code "9") (name "C2D") (class "Default")
      (node (ref "JP1") (pin "2") (pinfunction "2_2") (pintype "passive"))
      (node (ref "U2") (pin "10") (pinfunction "P3.0/C2D_10") (pintype "bidirectional"))
    )
    (net (code "10") (name "CHRG_0") (class "Default")
      (node (ref "R34") (pin "1") (pinfunction "1_1") (pintype "passive"))
      (node (ref "U2") (pin "17") (pinfunction "P1.5_17") (pintype "bidirectional"))
    )
    (net (code "11") (name "CHRG_1") (class "Default")
      (node (ref "R33") (pin "1") (pinfunction "1_1") (pintype "passive"))
      (node (ref "U2") (pin "16") (pinfunction "P1.6_16") (pintype "bidirectional"))
    )
    (net (code "12") (name "D+") (class "Default")
      (node (ref "R3") (pin "1") (pinfunction "1_1") (pintype "passive"))
      (node (ref "U1") (pin "D+") (pinfunction "D+_D+") (pintype "bidirectional"))
    )
    (net (code "13") (name "D-") (class "Default")
      (node (ref "R1") (pin "1") (pinfunction "1_1") (pintype "passive"))
      (node (ref "U1") (pin "D-") (pinfunction "D-_D-") (pintype "bidirectional"))
    )
    (net (code "14") (name "D{slash}~{C}") (class "Default")
      (node (ref "U2") (pin "27") (pinfunction "P0.3_27") (pintype "bidirectional"))
      (node (ref "U4") (pin "13") (pinfunction "D/~{C}_13") (pintype "input"))
      (node (ref "U4") (pin "5") (pinfunction "D/~{C}_5") (pintype "input"))
    )
    (net (code "15") (name "GATEDRV0") (class "Default")
      (node (ref "Q7") (pin "G2") (pinfunction "G_G2") (pintype "passive"))
      (node (ref "U6") (pin "5") (pinfunction "OUT_5") (pintype "output"))
    )
    (net (code "16") (name "GATEDRV1") (class "Default")
      (node (ref "Q7") (pin "G1") (pinfunction "G_G1") (pintype "passive"))
      (node (ref "U6") (pin "7") (pinfunction "OUT_7") (pintype "output"))
    )
    (net (code "17") (name "GND") (class "Default")
      (node (ref "C1") (pin "1") (pinfunction "1_1") (pintype "passive"))
      (node (ref "C10") (pin "1") (pinfunction "1_1") (pintype "passive"))
      (node (ref "C12") (pin "1") (pinfunction "1_1") (pintype "passive"))
      (node (ref "C13") (pin "1") (pinfunction "1_1") (pintype "passive"))
      (node (ref "C14") (pin "1") (pinfunction "1_1") (pintype "passive"))
      (node (ref "C15") (pin "1") (pinfunction "1_1") (pintype "passive"))
      (node (ref "C16") (pin "1") (pinfunction "1_1") (pintype "passive"))
      (node (ref "C17") (pin "2") (pinfunction "2_2") (pintype "passive"))
      (node (ref "C18") (pin "2") (pinfunction "2_2") (pintype "passive"))
      (node (ref "C19") (pin "2") (pinfunction "2_2") (pintype "passive"))
      (node (ref "C2") (pin "2") (pinfunction "2_2") (pintype "passive"))
      (node (ref "C20") (pin "2") (pinfunction "2_2") (pintype "passive"))
      (node (ref "C21") (pin "2") (pinfunction "2_2") (pintype "passive"))
      (node (ref "C22") (pin "2") (pinfunction "2_2") (pintype "passive"))
      (node (ref "C23") (pin "2") (pinfunction "2_2") (pintype "passive"))
      (node (ref "C25") (pin "1") (pinfunction "1_1") (pintype "passive"))
      (node (ref "C26") (pin "1") (pinfunction "1_1") (pintype "passive"))
      (node (ref "C27") (pin "1") (pinfunction "1_1") (pintype "passive"))
      (node (ref "C29") (pin "1") (pinfunction "1_1") (pintype "passive"))
      (node (ref "C3") (pin "1") (pinfunction "1_1") (pintype "passive"))
      (node (ref "C30") (pin "1") (pinfunction "1_1") (pintype "passive"))
      (node (ref "C31") (pin "1") (pinfunction "1_1") (pintype "passive"))
      (node (ref "C32") (pin "1") (pinfunction "1_1") (pintype "passive"))
      (node (ref "C33") (pin "1") (pinfunction "1_1") (pintype "passive"))
      (node (ref "C34") (pin "1") (pinfunction "1_1") (pintype "passive"))
      (node (ref "C35") (pin "1") (pinfunction "1_1") (pintype "passive"))
      (node (ref "C37") (pin "1") (pinfunction "1_1") (pintype "passive"))
      (node (ref "C39") (pin "1") (pinfunction "1_1") (pintype "passive"))
      (node (ref "C4") (pin "1") (pinfunction "1_1") (pintype "passive"))
      (node (ref "C40") (pin "1") (pinfunction "1_1") (pintype "passive"))
      (node (ref "C41") (pin "1") (pinfunction "1_1") (pintype "passive"))
      (node (ref "C42") (pin "1") (pinfunction "1_1") (pintype "passive"))
      (node (ref "C5") (pin "1") (pinfunction "1_1") (pintype "passive"))
      (node (ref "C7") (pin "1") (pinfunction "1_1") (pintype "passive"))
      (node (ref "C8") (pin "-") (pinfunction "-_-") (pintype "passive"))
      (node (ref "C9") (pin "1") (pinfunction "1_1") (pintype "passive"))
      (node (ref "D5") (pin "1") (pinfunction "A_1") (pintype "passive"))
      (node (ref "H1") (pin "B3,2") (pinfunction "MOUNT_B3,2") (pintype "passive"))
      (node (ref "H2") (pin "B3,2") (pinfunction "MOUNT_B3,2") (pintype "passive"))
      (node (ref "H3") (pin "B3,2") (pinfunction "MOUNT_B3,2") (pintype "passive"))
      (node (ref "H4") (pin "B3,2") (pinfunction "MOUNT_B3,2") (pintype "passive"))
      (node (ref "J1") (pin "2") (pinfunction "3_2") (pintype "passive"))
      (node (ref "J1") (pin "3") (pinfunction "2_3") (pintype "passive"))
      (node (ref "J4") (pin "4") (pinfunction "S_4") (pintype "passive"))
      (node (ref "J5") (pin "4") (pinfunction "S_4") (pintype "passive"))
      (node (ref "J7") (pin "2") (pinfunction "2_2") (pintype "passive"))
      (node (ref "JP1") (pin "4") (pinfunction "4_4") (pintype "passive"))
      (node (ref "JP2") (pin "1") (pinfunction "1_1") (pintype "passive"))
      (node (ref "L2") (pin "1") (pinfunction "1_1") (pintype "passive"))
      (node (ref "L3") (pin "2") (pinfunction "1_2") (pintype "passive"))
      (node (ref "L4") (pin "1") (pinfunction "1_1") (pintype "passive"))
      (node (ref "Q5") (pin "2") (pinfunction "E_2") (pintype "passive"))
      (node (ref "Q6") (pin "2") (pinfunction "E_2") (pintype "passive"))
      (node (ref "Q7") (pin "S1") (pinfunction "S_S1") (pintype "passive"))
      (node (ref "Q7") (pin "S2") (pinfunction "S_S2") (pintype "passive"))
      (node (ref "R18") (pin "1") (pinfunction "1_1") (pintype "passive"))
      (node (ref "R2") (pin "1") (pinfunction "1_1") (pintype "passive"))
      (node (ref "R21") (pin "1") (pinfunction "1_1") (pintype "passive"))
      (node (ref "R24") (pin "1") (pinfunction "1_1") (pintype "passive"))
      (node (ref "R25") (pin "1") (pinfunction "1_1") (pintype "passive"))
      (node (ref "R27") (pin "1") (pinfunction "1_1") (pintype "passive"))
      (node (ref "R32") (pin "2") (pinfunction "2_2") (pintype "passive"))
      (node (ref "R6") (pin "2") (pinfunction "2_2") (pintype "passive"))
      (node (ref "R9") (pin "1") (pinfunction "1_1") (pintype "passive"))
      (node (ref "S1") (pin "1") (pinfunction "1_1") (pintype "bidirectional"))
      (node (ref "S2") (pin "1") (pinfunction "1_1") (pintype "bidirectional"))
      (node (ref "S3") (pin "1") (pinfunction "1_1") (pintype "bidirectional"))
      (node (ref "TP3") (pin "TP") (pinfunction "TP_TP") (pintype "input"))
      (node (ref "U1") (pin "GND") (pinfunction "GND_GND") (pintype "bidirectional"))
      (node (ref "U1") (pin "S1") (pinfunction "S_S1") (pintype "bidirectional"))
      (node (ref "U1") (pin "S2") (pinfunction "S_S2") (pintype "bidirectional"))
      (node (ref "U1") (pin "S3") (pinfunction "S_S3") (pintype "bidirectional"))
      (node (ref "U1") (pin "S4") (pinfunction "S_S4") (pintype "bidirectional"))
      (node (ref "U2") (pin "3") (pinfunction "GND_3") (pintype "bidirectional"))
      (node (ref "U2") (pin "PAD") (pinfunction "GND_PAD") (pintype "bidirectional"))
      (node (ref "U3") (pin "2") (pinfunction "GND_2") (pintype "bidirectional"))
      (node (ref "U4") (pin "10") (pinfunction "GND_10") (pintype "input"))
      (node (ref "U4") (pin "11") (pinfunction "~{SCE}_11") (pintype "input"))
      (node (ref "U4") (pin "2") (pinfunction "GND_2") (pintype "input"))
      (node (ref "U4") (pin "3") (pinfunction "~{SCE}_3") (pintype "input"))
      (node (ref "U5") (pin "12") (pinfunction "GND_12") (pintype "power_in"))
      (node (ref "U6") (pin "3") (pinfunction "GND_3") (pintype "power_in"))
    )
    (net (code "18") (name "GPIO0") (class "Default")
      (node (ref "J4") (pin "2") (pinfunction "S_2") (pintype "passive"))
      (node (ref "RN1") (pin "8") (pinfunction "2_8") (pintype "passive"))
    )
    (net (code "19") (name "GPIO1") (class "Default")
      (node (ref "J5") (pin "2") (pinfunction "S_2") (pintype "passive"))
      (node (ref "RN1") (pin "6") (pinfunction "2_6") (pintype "passive"))
    )
    (net (code "20") (name "GPIO2") (class "Default")
      (node (ref "TP1") (pin "TP") (pinfunction "TP_TP") (pintype "input"))
      (node (ref "U2") (pin "15") (pinfunction "P1.7_15") (pintype "bidirectional"))
    )
    (net (code "21") (name "IBAT0") (class "Default")
      (node (ref "C20") (pin "1") (pinfunction "1_1") (pintype "passive"))
      (node (ref "RN3") (pin "3") (pinfunction "1_3") (pintype "passive"))
      (node (ref "U2") (pin "19") (pinfunction "P1.3_19") (pintype "bidirectional"))
    )
    (net (code "22") (name "IBAT1") (class "Default")
      (node (ref "C22") (pin "1") (pinfunction "1_1") (pintype "passive"))
      (node (ref "RN3") (pin "4") (pinfunction "1_4") (pintype "passive"))
      (node (ref "U2") (pin "18") (pinfunction "P1.4_18") (pintype "bidirectional"))
    )
    (net (code "23") (name "LOAD") (class "Default")
      (node (ref "J7") (pin "1") (pinfunction "1_1") (pintype "passive"))
      (node (ref "K1") (pin "3") (pinfunction "O_3") (pintype "passive"))
      (node (ref "K2") (pin "10") (pinfunction "O_10") (pintype "passive"))
    )
    (net (code "24") (name "MISO") (class "Default")
      (node (ref "R11") (pin "1") (pinfunction "1_1") (pintype "passive"))
      (node (ref "U2") (pin "1") (pinfunction "P0.1_1") (pintype "bidirectional"))
    )
    (net (code "25") (name "MOSI") (class "Default")
      (node (ref "U2") (pin "28") (pinfunction "P0.2_28") (pintype "bidirectional"))
      (node (ref "U4") (pin "14") (pinfunction "SDIN_14") (pintype "input"))
      (node (ref "U4") (pin "6") (pinfunction "SDIN_6") (pintype "input"))
    )
    (net (code "26") (name "Net-(C1-Pad2)") (class "Default")
      (node (ref "C1") (pin "2") (pinfunction "2_2") (pintype "passive"))
      (node (ref "D2") (pin "A") (pinfunction "A_A") (pintype "passive"))
      (node (ref "J1") (pin "1") (pinfunction "1_1") (pintype "passive"))
    )
    (net (code "27") (name "Net-(C10-Pad2)") (class "Default")
      (node (ref "C10") (pin "2") (pinfunction "2_2") (pintype "passive"))
      (node (ref "R10") (pin "2") (pinfunction "2_2") (pintype "passive"))
      (node (ref "R11") (pin "2") (pinfunction "2_2") (pintype "passive"))
      (node (ref "U4") (pin "12") (pinfunction "~{RES}_12") (pintype "input"))
      (node (ref "U4") (pin "4") (pinfunction "~{RES}_4") (pintype "input"))
    )
    (net (code "28") (name "Net-(C11-Pad2)") (class "Default")
      (node (ref "C11") (pin "2") (pinfunction "2_2") (pintype "passive"))
      (node (ref "D4") (pin "A") (pinfunction "A_A") (pintype "passive"))
      (node (ref "L2") (pin "2") (pinfunction "2_2") (pintype "passive"))
    )
    (net (code "29") (name "Net-(D3-A1)") (class "Default")
      (node (ref "C11") (pin "1") (pinfunction "1_1") (pintype "passive"))
      (node (ref "D3") (pin "1") (pinfunction "A1_1") (pintype "passive"))
      (node (ref "D3") (pin "2") (pinfunction "A2_2") (pintype "passive"))
      (node (ref "L1") (pin "1") (pinfunction "1_1") (pintype "passive"))
      (node (ref "U3") (pin "1") (pinfunction "SW_1") (pintype "bidirectional"))
    )
    (net (code "30") (name "Net-(D3-CC)") (class "Default")
      (node (ref "C12") (pin "2") (pinfunction "2_2") (pintype "passive"))
      (node (ref "D3") (pin "3") (pinfunction "CC_3") (pintype "passive"))
      (node (ref "Q3") (pin "3") (pinfunction "C_3") (pintype "passive"))
      (node (ref "R14") (pin "2") (pinfunction "2_2") (pintype "passive"))
    )
    (net (code "31") (name "Net-(D5-K)") (class "Default")
      (node (ref "D5") (pin "3") (pinfunction "K_3") (pintype "passive"))
      (node (ref "Q3") (pin "1") (pinfunction "B_1") (pintype "passive"))
      (node (ref "R14") (pin "1") (pinfunction "1_1") (pintype "passive"))
    )
    (net (code "32") (name "Net-(D6-A)") (class "Default")
      (node (ref "D6") (pin "1") (pinfunction "A_1") (pintype "passive"))
      (node (ref "R16") (pin "1") (pinfunction "1_1") (pintype "passive"))
      (node (ref "R17") (pin "2") (pinfunction "2_2") (pintype "passive"))
      (node (ref "RN3") (pin "5") (pinfunction "2_5") (pintype "passive"))
    )
    (net (code "33") (name "Net-(D7-A)") (class "Default")
      (node (ref "D7") (pin "1") (pinfunction "A_1") (pintype "passive"))
      (node (ref "R19") (pin "2") (pinfunction "2_2") (pintype "passive"))
      (node (ref "R20") (pin "2") (pinfunction "2_2") (pintype "passive"))
      (node (ref "RN3") (pin "6") (pinfunction "2_6") (pintype "passive"))
    )
    (net (code "34") (name "Net-(D8-A)") (class "Default")
      (node (ref "D8") (pin "1") (pinfunction "A_1") (pintype "passive"))
      (node (ref "K1") (pin "12") (pinfunction "-_12") (pintype "passive"))
      (node (ref "Q5") (pin "3") (pinfunction "C_3") (pintype "passive"))
    )
    (net (code "35") (name "Net-(D9-A)") (class "Default")
      (node (ref "D9") (pin "1") (pinfunction "A_1") (pintype "passive"))
      (node (ref "K2") (pin "12") (pinfunction "-_12") (pintype "passive"))
      (node (ref "Q6") (pin "3") (pinfunction "C_3") (pintype "passive"))
    )
    (net (code "36") (name "Net-(J2-Pad1)") (class "Default")
      (node (ref "J2") (pin "1") (pinfunction "1_1") (pintype "passive"))
      (node (ref "R15") (pin "1") (pinfunction "1_1") (pintype "passive"))
    )
    (net (code "37") (name "Net-(J4A-S)") (class "Default")
      (node (ref "C17") (pin "1") (pinfunction "1_1") (pintype "passive"))
      (node (ref "J2") (pin "2") (pinfunction "2_2") (pintype "passive"))
      (node (ref "J4") (pin "1") (pinfunction "S_1") (pintype "passive"))
      (node (ref "J5") (pin "1") (pinfunction "S_1") (pintype "passive"))
    )
    (net (code "38") (name "Net-(K1B-P)") (class "Default")
      (node (ref "C41") (pin "2") (pinfunction "2_2") (pintype "passive"))
      (node (ref "D11") (pin "K") (pinfunction "K_K") (pintype "passive"))
      (node (ref "K1") (pin "4") (pinfunction "P_4") (pintype "passive"))
    )
    (net (code "39") (name "Net-(K1C-O)") (class "Default")
      (node (ref "D13") (pin "K") (pinfunction "K_K") (pintype "passive"))
      (node (ref "K1") (pin "10") (pinfunction "O_10") (pintype "passive"))
    )
    (net (code "40") (name "Net-(K1C-P)") (class "Default")
      (node (ref "C39") (pin "2") (pinfunction "2_2") (pintype "passive"))
      (node (ref "K1") (pin "9") (pinfunction "P_9") (pintype "passive"))
      (node (ref "L3") (pin "1") (pinfunction "1_1") (pintype "passive"))
    )
    (net (code "41") (name "Net-(K2B-O)") (class "Default")
      (node (ref "D12") (pin "K") (pinfunction "K_K") (pintype "passive"))
      (node (ref "K2") (pin "3") (pinfunction "O_3") (pintype "passive"))
    )
    (net (code "42") (name "Net-(K2B-P)") (class "Default")
      (node (ref "C37") (pin "2") (pinfunction "2_2") (pintype "passive"))
      (node (ref "K2") (pin "4") (pinfunction "P_4") (pintype "passive"))
      (node (ref "L4") (pin "2") (pinfunction "1_2") (pintype "passive"))
    )
    (net (code "43") (name "Net-(K2C-P)") (class "Default")
      (node (ref "C40") (pin "2") (pinfunction "2_2") (pintype "passive"))
      (node (ref "D10") (pin "K") (pinfunction "K_K") (pintype "passive"))
      (node (ref "K2") (pin "9") (pinfunction "P_9") (pintype "passive"))
    )
    (net (code "44") (name "Net-(L3A-2)") (class "Default")
      (node (ref "C38") (pin "2") (pinfunction "2_2") (pintype "passive"))
      (node (ref "L3") (pin "3") (pinfunction "2_3") (pintype "passive"))
      (node (ref "Q7") (pin "D1@1") (pinfunction "D_D1@1") (pintype "passive"))
      (node (ref "Q7") (pin "D1@2") (pinfunction "D_D1@2") (pintype "passive"))
    )
    (net (code "45") (name "Net-(L3B-2)") (class "Default")
      (node (ref "C38") (pin "1") (pinfunction "1_1") (pintype "passive"))
      (node (ref "D11") (pin "A") (pinfunction "A_A") (pintype "passive"))
      (node (ref "L3") (pin "4") (pinfunction "2_4") (pintype "passive"))
    )
    (net (code "46") (name "Net-(L4A-2)") (class "Default")
      (node (ref "C36") (pin "1") (pinfunction "1_1") (pintype "passive"))
      (node (ref "D10") (pin "A") (pinfunction "A_A") (pintype "passive"))
      (node (ref "L4") (pin "3") (pinfunction "2_3") (pintype "passive"))
    )
    (net (code "47") (name "Net-(L4B-2)") (class "Default")
      (node (ref "C36") (pin "2") (pinfunction "2_2") (pintype "passive"))
      (node (ref "L4") (pin "4") (pinfunction "2_4") (pintype "passive"))
      (node (ref "Q7") (pin "D2@1") (pinfunction "D_D2@1") (pintype "passive"))
      (node (ref "Q7") (pin "D2@2") (pinfunction "D_D2@2") (pintype "passive"))
    )
    (net (code "48") (name "Net-(Q1-B)") (class "Default")
      (node (ref "Q1") (pin "1") (pinfunction "B_1") (pintype "passive"))
      (node (ref "R7") (pin "2") (pinfunction "2_2") (pintype "passive"))
    )
    (net (code "49") (name "Net-(Q1-C)") (class "Default")
      (node (ref "C6") (pin "2") (pinfunction "2_2") (pintype "passive"))
      (node (ref "Q1") (pin "3") (pinfunction "C_3") (pintype "passive"))
      (node (ref "Q2") (pin "1") (pinfunction "G_1") (pintype "passive"))
      (node (ref "R6") (pin "1") (pinfunction "1_1") (pintype "passive"))
    )
    (net (code "50") (name "Net-(Q2-D)") (class "Default")
      (node (ref "C8") (pin "+") (pinfunction "+_+") (pintype "passive"))
      (node (ref "Q2") (pin "3") (pinfunction "D_3") (pintype "passive"))
      (node (ref "R7") (pin "1") (pinfunction "1_1") (pintype "passive"))
      (node (ref "R8") (pin "1") (pinfunction "1_1") (pintype "passive"))
    )
    (net (code "51") (name "Net-(Q4-B)") (class "Default")
      (node (ref "C24") (pin "1") (pinfunction "1_1") (pintype "passive"))
      (node (ref "Q4") (pin "1") (pinfunction "B_1") (pintype "passive"))
      (node (ref "R26") (pin "1") (pinfunction "1_1") (pintype "passive"))
      (node (ref "R27") (pin "2") (pinfunction "2_2") (pintype "passive"))
    )
    (net (code "52") (name "Net-(Q4-C)") (class "Default")
      (node (ref "C25") (pin "2") (pinfunction "2_2") (pintype "passive"))
      (node (ref "C28") (pin "1") (pinfunction "1_1") (pintype "passive"))
      (node (ref "Q4") (pin "3") (pinfunction "C_3") (pintype "passive"))
      (node (ref "U5") (pin "2") (pinfunction "OUT_2") (pintype "open_collector"))
      (node (ref "U5") (pin "4") (pinfunction "-IN_4") (pintype "input"))
      (node (ref "U5") (pin "7") (pinfunction "+IN_7") (pintype "input"))
      (node (ref "U5") (pin "9") (pinfunction "+IN_9") (pintype "input"))
    )
    (net (code "53") (name "Net-(Q4-E)") (class "Default")
      (node (ref "Q4") (pin "2") (pinfunction "E_2") (pintype "passive"))
      (node (ref "R30") (pin "1") (pinfunction "1_1") (pintype "passive"))
    )
    (net (code "54") (name "Net-(Q5-B)") (class "Default")
      (node (ref "Q5") (pin "1") (pinfunction "B_1") (pintype "passive"))
      (node (ref "R33") (pin "2") (pinfunction "2_2") (pintype "passive"))
    )
    (net (code "55") (name "Net-(Q6-B)") (class "Default")
      (node (ref "Q6") (pin "1") (pinfunction "B_1") (pintype "passive"))
      (node (ref "R34") (pin "2") (pinfunction "2_2") (pintype "passive"))
    )
    (net (code "56") (name "Net-(R4-Pad2)") (class "Default")
      (node (ref "R4") (pin "2") (pinfunction "2_2") (pintype "passive"))
      (node (ref "S1") (pin "2") (pinfunction "2_2") (pintype "bidirectional"))
    )
    (net (code "57") (name "Net-(R13-Pad1)") (class "Default")
      (node (ref "R13") (pin "1") (pinfunction "1_1") (pintype "passive"))
      (node (ref "U4") (pin "16") (pinfunction "LED_16") (pintype "input"))
      (node (ref "U4") (pin "8") (pinfunction "LED_8") (pintype "input"))
    )
    (net (code "58") (name "Net-(RN1B-1)") (class "Default")
      (node (ref "RN1") (pin "2") (pinfunction "1_2") (pintype "passive"))
      (node (ref "U2") (pin "13") (pinfunction "P2.1_13") (pintype "bidirectional"))
    )
    (net (code "59") (name "Net-(RN1C-1)") (class "Default")
      (node (ref "RN1") (pin "3") (pinfunction "1_3") (pintype "passive"))
      (node (ref "U2") (pin "12") (pinfunction "P2.2_12") (pintype "bidirectional"))
    )
    (net (code "60") (name "Net-(RN1D-1)") (class "Default")
      (node (ref "RN1") (pin "4") (pinfunction "1_4") (pintype "passive"))
      (node (ref "U2") (pin "11") (pinfunction "P2.3_11") (pintype "bidirectional"))
    )
    (net (code "61") (name "Net-(RN2-Pad1)") (class "Default")
      (node (ref "RN2") (pin "1") (pinfunction "1_1") (pintype "passive"))
      (node (ref "S3") (pin "2") (pinfunction "2_2") (pintype "bidirectional"))
    )
    (net (code "62") (name "Net-(RN2B-1)") (class "Default")
      (node (ref "RN2") (pin "2") (pinfunction "1_2") (pintype "passive"))
      (node (ref "RN2") (pin "3") (pinfunction "1_3") (pintype "passive"))
      (node (ref "S2") (pin "2") (pinfunction "2_2") (pintype "bidirectional"))
    )
    (net (code "63") (name "Net-(RN4A-2)") (class "Default")
      (node (ref "C29") (pin "2") (pinfunction "2_2") (pintype "passive"))
      (node (ref "RN4") (pin "2") (pinfunction "1_2") (pintype "passive"))
      (node (ref "RN4") (pin "8") (pinfunction "2_8") (pintype "passive"))
    )
    (net (code "64") (name "Net-(RN4B-2)") (class "Default")
      (node (ref "C26") (pin "2") (pinfunction "2_2") (pintype "passive"))
      (node (ref "R28") (pin "1") (pinfunction "1_1") (pintype "passive"))
      (node (ref "RN4") (pin "7") (pinfunction "2_7") (pintype "passive"))
    )
    (net (code "65") (name "Net-(RN4C-1)") (class "Default")
      (node (ref "C30") (pin "2") (pinfunction "2_2") (pintype "passive"))
      (node (ref "RN4") (pin "3") (pinfunction "1_3") (pintype "passive"))
      (node (ref "RN4") (pin "5") (pinfunction "2_5") (pintype "passive"))
    )
    (net (code "66") (name "Net-(RN4C-2)") (class "Default")
      (node (ref "C27") (pin "2") (pinfunction "2_2") (pintype "passive"))
      (node (ref "R29") (pin "1") (pinfunction "1_1") (pintype "passive"))
      (node (ref "RN4") (pin "6") (pinfunction "2_6") (pintype "passive"))
    )
    (net (code "67") (name "Net-(U2-D+)") (class "Default")
      (node (ref "R3") (pin "2") (pinfunction "2_2") (pintype "passive"))
      (node (ref "U2") (pin "4") (pinfunction "D+_4") (pintype "bidirectional"))
    )
    (net (code "68") (name "Net-(U2-D-)") (class "Default")
      (node (ref "R1") (pin "2") (pinfunction "2_2") (pintype "passive"))
      (node (ref "U2") (pin "5") (pinfunction "D-_5") (pintype "bidirectional"))
    )
    (net (code "69") (name "Net-(U2-P2.0)") (class "Default")
      (node (ref "RN1") (pin "1") (pinfunction "1_1") (pintype "passive"))
      (node (ref "U2") (pin "14") (pinfunction "P2.0_14") (pintype "bidirectional"))
    )
    (net (code "70") (name "Net-(U2-P3.1{slash}VBUS)") (class "Default")
      (node (ref "C5") (pin "2") (pinfunction "2_2") (pintype "passive"))
      (node (ref "R2") (pin "2") (pinfunction "2_2") (pintype "passive"))
      (node (ref "R37") (pin "1") (pinfunction "1_1") (pintype "passive"))
      (node (ref "U2") (pin "8") (pinfunction "P3.1/VBUS_8") (pintype "bidirectional"))
    )
    (net (code "71") (name "Net-(U3-FB)") (class "Default")
      (node (ref "R12") (pin "1") (pinfunction "1_1") (pintype "passive"))
      (node (ref "R9") (pin "2") (pinfunction "2_2") (pintype "passive"))
      (node (ref "U3") (pin "3") (pinfunction "FB_3") (pintype "bidirectional"))
    )
    (net (code "72") (name "Net-(U5A-+IN)") (class "Default")
      (node (ref "C28") (pin "2") (pinfunction "2_2") (pintype "passive"))
      (node (ref "R31") (pin "1") (pinfunction "1_1") (pintype "passive"))
      (node (ref "R32") (pin "1") (pinfunction "1_1") (pintype "passive"))
      (node (ref "U5") (pin "5") (pinfunction "+IN_5") (pintype "input"))
    )
    (net (code "73") (name "Net-(U5B-OUT)") (class "Default")
      (node (ref "R35") (pin "2") (pinfunction "2_2") (pintype "passive"))
      (node (ref "U5") (pin "1") (pinfunction "OUT_1") (pintype "open_collector"))
      (node (ref "U6") (pin "2") (pinfunction "~{IN}_2") (pintype "input"))
    )
    (net (code "74") (name "Net-(U5C-OUT)") (class "Default")
      (node (ref "R36") (pin "1") (pinfunction "1_1") (pintype "passive"))
      (node (ref "U5") (pin "14") (pinfunction "OUT_14") (pintype "open_collector"))
      (node (ref "U6") (pin "4") (pinfunction "~{IN}_4") (pintype "input"))
    )
    (net (code "75") (name "PWM0") (class "Default")
      (node (ref "R28") (pin "2") (pinfunction "2_2") (pintype "passive"))
      (node (ref "U2") (pin "23") (pinfunction "P0.7_23") (pintype "bidirectional"))
    )
    (net (code "76") (name "PWM0_REF") (class "Default")
      (node (ref "C31") (pin "2") (pinfunction "2_2") (pintype "passive"))
      (node (ref "RN4") (pin "1") (pinfunction "1_1") (pintype "passive"))
      (node (ref "U5") (pin "8") (pinfunction "-IN_8") (pintype "input"))
    )
    (net (code "77") (name "PWM1") (class "Default")
      (node (ref "R29") (pin "2") (pinfunction "2_2") (pintype "passive"))
      (node (ref "U2") (pin "22") (pinfunction "P1.0_22") (pintype "bidirectional"))
    )
    (net (code "78") (name "PWM1_REF") (class "Default")
      (node (ref "C32") (pin "2") (pinfunction "2_2") (pintype "passive"))
      (node (ref "RN4") (pin "4") (pinfunction "1_4") (pintype "passive"))
      (node (ref "U5") (pin "6") (pinfunction "-IN_6") (pintype "input"))
    )
    (net (code "79") (name "RXD0") (class "Default")
      (node (ref "JP2") (pin "2") (pinfunction "2_2") (pintype "passive"))
      (node (ref "U2") (pin "25") (pinfunction "P0.5_25") (pintype "bidirectional"))
    )
    (net (code "80") (name "SCK") (class "Default")
      (node (ref "U2") (pin "2") (pinfunction "P0.0_2") (pintype "bidirectional"))
      (node (ref "U4") (pin "15") (pinfunction "SCK_15") (pintype "input"))
      (node (ref "U4") (pin "7") (pinfunction "SCK_7") (pintype "input"))
    )
    (net (code "81") (name "THEM0") (class "Default")
      (node (ref "J4") (pin "3") (pinfunction "S_3") (pintype "passive"))
      (node (ref "RN1") (pin "7") (pinfunction "2_7") (pintype "passive"))
      (node (ref "RN3") (pin "7") (pinfunction "2_7") (pintype "passive"))
    )
    (net (code "82") (name "THEM1") (class "Default")
      (node (ref "J5") (pin "3") (pinfunction "S_3") (pintype "passive"))
      (node (ref "RN1") (pin "5") (pinfunction "2_5") (pintype "passive"))
      (node (ref "RN3") (pin "8") (pinfunction "2_8") (pintype "passive"))
    )
    (net (code "83") (name "TXD0") (class "Default")
      (node (ref "JP2") (pin "3") (pinfunction "3_3") (pintype "passive"))
      (node (ref "U2") (pin "26") (pinfunction "P0.4_26") (pintype "bidirectional"))
    )
    (net (code "84") (name "VBAT0") (class "Default")
      (node (ref "C21") (pin "1") (pinfunction "1_1") (pintype "passive"))
      (node (ref "R22") (pin "1") (pinfunction "1_1") (pintype "passive"))
      (node (ref "R24") (pin "2") (pinfunction "2_2") (pintype "passive"))
      (node (ref "U2") (pin "21") (pinfunction "P1.1_21") (pintype "bidirectional"))
    )
    (net (code "85") (name "VBAT1") (class "Default")
      (node (ref "C23") (pin "1") (pinfunction "1_1") (pintype "passive"))
      (node (ref "R23") (pin "1") (pinfunction "1_1") (pintype "passive"))
      (node (ref "R25") (pin "2") (pinfunction "2_2") (pintype "passive"))
      (node (ref "U2") (pin "20") (pinfunction "P1.2_20") (pintype "bidirectional"))
    )
    (net (code "86") (name "VBUS") (class "Default")
      (node (ref "C2") (pin "1") (pinfunction "1_1") (pintype "passive"))
      (node (ref "D1") (pin "A") (pinfunction "A_A") (pintype "passive"))
      (node (ref "U1") (pin "VBUS1") (pinfunction "VBUS_VBUS1") (pintype "bidirectional"))
    )
    (net (code "87") (name "VCC") (class "Default")
      (node (ref "C6") (pin "1") (pinfunction "1_1") (pintype "passive"))
      (node (ref "C9") (pin "2") (pinfunction "2_2") (pintype "passive"))
      (node (ref "D1") (pin "K") (pinfunction "K_K") (pintype "passive"))
      (node (ref "D2") (pin "K") (pinfunction "K_K") (pintype "passive"))
      (node (ref "K1") (pin "8") (pinfunction "S_8") (pintype "passive"))
      (node (ref "K2") (pin "5") (pinfunction "S_5") (pintype "passive"))
      (node (ref "L1") (pin "2") (pinfunction "2_2") (pintype "passive"))
      (node (ref "Q1") (pin "2") (pinfunction "E_2") (pintype "passive"))
      (node (ref "Q2") (pin "2") (pinfunction "S_2") (pintype "passive"))
      (node (ref "R37") (pin "2") (pinfunction "2_2") (pintype "passive"))
      (node (ref "R8") (pin "2") (pinfunction "2_2") (pintype "passive"))
      (node (ref "U3") (pin "4") (pinfunction "~{SHDN}_4") (pintype "bidirectional"))
      (node (ref "U3") (pin "5") (pinfunction "VIN_5") (pintype "bidirectional"))
    )
    (net (code "88") (name "VPP") (class "Default")
      (node (ref "C15") (pin "2") (pinfunction "2_2") (pintype "passive"))
      (node (ref "C16") (pin "2") (pinfunction "2_2") (pintype "passive"))
      (node (ref "C35") (pin "2") (pinfunction "2_2") (pintype "passive"))
      (node (ref "Q3") (pin "2") (pinfunction "E_2") (pintype "passive"))
      (node (ref "R35") (pin "1") (pinfunction "1_1") (pintype "passive"))
      (node (ref "R36") (pin "2") (pinfunction "2_2") (pintype "passive"))
      (node (ref "U6") (pin "6") (pinfunction "VCC_6") (pintype "power_in"))
    )
    (net (code "89") (name "unconnected-(U1-USBID-PadID1)") (class "Default")
      (node (ref "U1") (pin "ID1") (pinfunction "USBID_ID1") (pintype "bidirectional"))
    )
  )
)
